# Antenna.net
KiCad netlist of a schematic drawn in Altium Designer
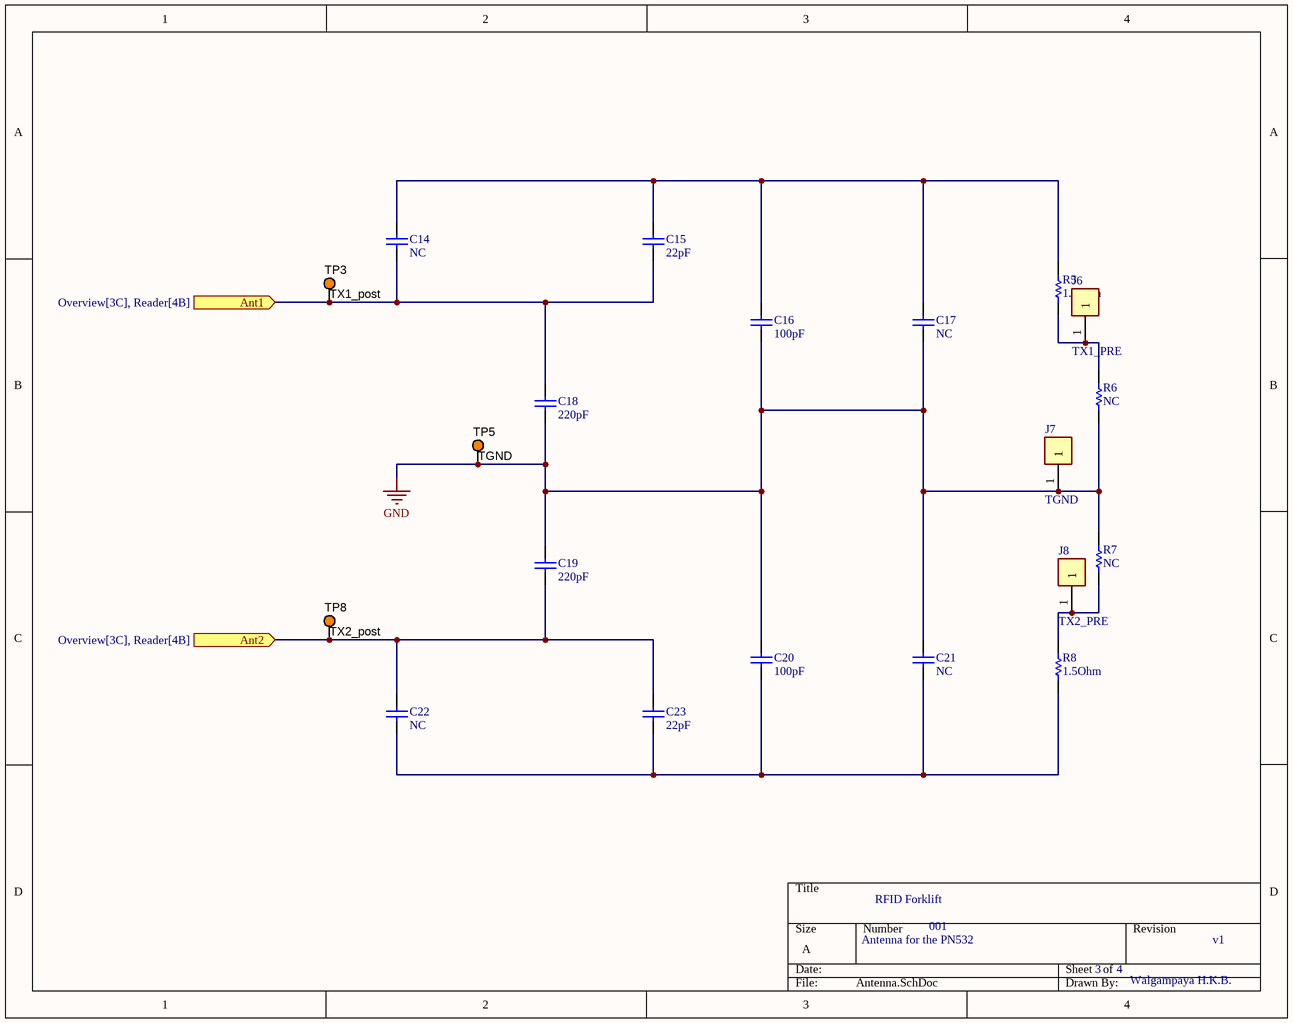
[diagram p0: Antenna.SchDoc]

(export (version "E")
  (design (tool "Eeschema 10.0.6"))
  (components
    (comp (ref "C14")
      (value "NC")
      (footprint "CAPC2013X140X50LL20T25")
      (description "08055C221KAT2A")
      (fields (field (name "MANUFACTURER") "AVX Interconnect / Elco"))
      (libsource (lib "Altium Content Vault") (part "CAP"))
    )
    (comp (ref "C15")
      (value "22pF")
      (footprint "CAPC2013X140X50LL20T25")
      (description "08055C221KAT2A")
      (fields (field (name "MANUFACTURER") "AVX Interconnect / Elco"))
      (libsource (lib "Altium Content Vault") (part "CAP"))
    )
    (comp (ref "C16")
      (value "100pF")
      (footprint "CAPC2013X140X50LL20T25")
      (description "08055C221KAT2A\r\n0805")
      (fields
        (field (name "PART NUMBER") "08055C221KAT2A")
        (field (name "MANUFACTURER") "AVX Interconnect / Elco")
      )
      (libsource (lib "Altium Content Vault") (part "CAP"))
    )
    (comp (ref "C17")
      (value "NC")
      (footprint "CAPC2013X140X50LL20T25")
      (description "08055C221KAT2A")
      (fields (field (name "MANUFACTURER") "AVX Interconnect / Elco"))
      (libsource (lib "Altium Content Vault") (part "CAP"))
    )
    (comp (ref "C18")
      (value "220pF")
      (footprint "CAPC2013X140X50LL20T25")
      (description "08055C221KAT2A")
      (fields (field (name "MANUFACTURER") "AVX Interconnect / Elco"))
      (libsource (lib "Altium Content Vault") (part "CAP"))
    )
    (comp (ref "C19")
      (value "220pF")
      (footprint "CAPC2013X140X50LL20T25")
      (description "08055C221KAT2A")
      (fields (field (name "MANUFACTURER") "AVX Interconnect / Elco"))
      (libsource (lib "Altium Content Vault") (part "CAP"))
    )
    (comp (ref "C20")
      (value "100pF")
      (footprint "CAPC2013X140X50LL20T25")
      (description "08055C221KAT2A")
      (fields (field (name "MANUFACTURER") "AVX Interconnect / Elco"))
      (libsource (lib "Altium Content Vault") (part "CAP"))
    )
    (comp (ref "C21")
      (value "NC")
      (footprint "CAPC2013X140X50LL20T25")
      (description "08055C221KAT2A")
      (fields (field (name "MANUFACTURER") "AVX Interconnect / Elco"))
      (libsource (lib "Altium Content Vault") (part "CAP"))
    )
    (comp (ref "C22")
      (value "NC")
      (footprint "CAPC2013X140X50LL20T25")
      (description "08055C221KAT2A")
      (fields (field (name "MANUFACTURER") "AVX Interconnect / Elco"))
      (libsource (lib "Altium Content Vault") (part "CAP"))
    )
    (comp (ref "C23")
      (value "22pF")
      (footprint "CAPC2013X140X50LL20T25")
      (description "08055C221KAT2A")
      (fields (field (name "MANUFACTURER") "AVX Interconnect / Elco"))
      (libsource (lib "Altium Content Vault") (part "CAP"))
    )
    (comp (ref "J6")
      (value "TX1_PRE")
      (footprint "PN532_final:FP-5000-MFG")
      (description "PC TEST POINT MINIATURE RED")
      (libsource (lib "PN532_final") (part "CMP-19636-000027-1"))
    )
    (comp (ref "J7")
      (value "TGND")
      (footprint "PN532_final:FP-5000-MFG")
      (description "PC TEST POINT MINIATURE RED")
      (libsource (lib "PN532_final") (part "CMP-19636-000027-1"))
    )
    (comp (ref "J8")
      (value "TX2_PRE")
      (footprint "PN532_final:FP-5000-MFG")
      (description "PC TEST POINT MINIATURE RED")
      (libsource (lib "PN532_final") (part "CMP-19636-000027-1"))
    )
    (comp (ref "R5")
      (value "1.5Ohm")
      (footprint "RESC3116X65X40ML10T20")
      (description "Chip Resistor, 10 Ohm, +/- 1%, 0.25 W, -55 to 155 degC, 1206 (3216 Metric), RoHS, Tape and Reel")
      (fields (field (name "MANUFACTURER") "Yageo") (field (name "TOLERANCE") "1%"))
      (libsource (lib "Altium Content Vault") (part "RES-2"))
    )
    (comp (ref "R6")
      (value "NC")
      (footprint "RESC1005X40X25ML05T10")
      (fields (field (name "PART NUMBER") "RC0402FR-07100RL") (field (name "MANUFACTURER") "Yageo / Phycomp"))
      (libsource (lib "Altium Content Vault") (part "RES"))
    )
    (comp (ref "R7")
      (value "NC")
      (footprint "RESC1005X40X25ML05T10")
      (fields (field (name "PART NUMBER") "RC0402FR-07100RL") (field (name "MANUFACTURER") "Yageo / Phycomp"))
      (libsource (lib "Altium Content Vault") (part "RES"))
    )
    (comp (ref "R8")
      (value "1.5Ohm")
      (footprint "RESC3116X65X40ML10T20")
      (description "Chip Resistor, 10 Ohm, +/- 1%, 0.25 W, -55 to 155 degC, 1206 (3216 Metric), RoHS, Tape and Reel")
      (fields (field (name "MANUFACTURER") "Yageo") (field (name "TOLERANCE") "1%"))
      (libsource (lib "Altium Content Vault") (part "RES-2"))
    )
    (comp (ref "TP3")
      (value "TX1_post")
      (footprint "KSTN-5003")
      (description "Test Point, Orange, 1-Pin THD, RoHS")
      (libsource (lib "Altium Content Vault") (part "TESTPOINT_ORANGE"))
    )
    (comp (ref "TP5")
      (value "TGND")
      (footprint "KSTN-5003")
      (description "Test Point, Orange, 1-Pin THD, RoHS")
      (libsource (lib "Altium Content Vault") (part "TESTPOINT_ORANGE"))
    )
    (comp (ref "TP8")
      (value "TX2_post")
      (footprint "KSTN-5003")
      (description "Test Point, Orange, 1-Pin THD, RoHS")
      (libsource (lib "Altium Content Vault") (part "TESTPOINT_ORANGE"))
    )
  )
  (nets
    (net (code "1") (name "/Ant1") (class "Default")
      (node (ref "C14") (pin "1") (pinfunction "1_1") (pintype "passive"))
      (node (ref "C15") (pin "1") (pinfunction "1_1") (pintype "passive"))
      (node (ref "C18") (pin "2") (pinfunction "2_2") (pintype "passive"))
      (node (ref "TP3") (pin "1") (pinfunction "1_1") (pintype "passive"))
    )
    (net (code "2") (name "/Ant2") (class "Default")
      (node (ref "C19") (pin "1") (pinfunction "1_1") (pintype "passive"))
      (node (ref "C22") (pin "2") (pinfunction "2_2") (pintype "passive"))
      (node (ref "C23") (pin "2") (pinfunction "2_2") (pintype "passive"))
      (node (ref "TP8") (pin "1") (pinfunction "1_1") (pintype "passive"))
    )
    (net (code "3") (name "GND") (class "Default")
      (node (ref "C16") (pin "1") (pinfunction "1_1") (pintype "passive"))
      (node (ref "C17") (pin "1") (pinfunction "1_1") (pintype "passive"))
      (node (ref "C18") (pin "1") (pinfunction "1_1") (pintype "passive"))
      (node (ref "C19") (pin "2") (pinfunction "2_2") (pintype "passive"))
      (node (ref "C20") (pin "2") (pinfunction "2_2") (pintype "passive"))
      (node (ref "C21") (pin "2") (pinfunction "2_2") (pintype "passive"))
      (node (ref "J7") (pin "1") (pinfunction "1_1") (pintype "passive"))
      (node (ref "R6") (pin "1") (pinfunction "1_1") (pintype "passive"))
      (node (ref "R7") (pin "2") (pinfunction "2_2") (pintype "passive"))
      (node (ref "TP5") (pin "1") (pinfunction "1_1") (pintype "passive"))
    )
    (net (code "4") (name "Net-(C14-Pad2)") (class "Default")
      (node (ref "C14") (pin "2") (pinfunction "2_2") (pintype "passive"))
      (node (ref "C15") (pin "2") (pinfunction "2_2") (pintype "passive"))
      (node (ref "C16") (pin "2") (pinfunction "2_2") (pintype "passive"))
      (node (ref "C17") (pin "2") (pinfunction "2_2") (pintype "passive"))
      (node (ref "R5") (pin "2") (pinfunction "2_2") (pintype "passive"))
    )
    (net (code "5") (name "Net-(C20-Pad1)") (class "Default")
      (node (ref "C20") (pin "1") (pinfunction "1_1") (pintype "passive"))
      (node (ref "C21") (pin "1") (pinfunction "1_1") (pintype "passive"))
      (node (ref "C22") (pin "1") (pinfunction "1_1") (pintype "passive"))
      (node (ref "C23") (pin "1") (pinfunction "1_1") (pintype "passive"))
      (node (ref "R8") (pin "1") (pinfunction "1_1") (pintype "passive"))
    )
    (net (code "6") (name "Net-(J6-Pad1)") (class "Default")
      (node (ref "J6") (pin "1") (pinfunction "1_1") (pintype "passive"))
      (node (ref "R5") (pin "1") (pinfunction "1_1") (pintype "passive"))
      (node (ref "R6") (pin "2") (pinfunction "2_2") (pintype "passive"))
    )
    (net (code "7") (name "Net-(J8-Pad1)") (class "Default")
      (node (ref "J8") (pin "1") (pinfunction "1_1") (pintype "passive"))
      (node (ref "R7") (pin "1") (pinfunction "1_1") (pintype "passive"))
      (node (ref "R8") (pin "2") (pinfunction "2_2") (pintype "passive"))
    )
  )
)
